# ap-pam-VX.net
KiCad netlist of a schematic drawn in Altium Designer
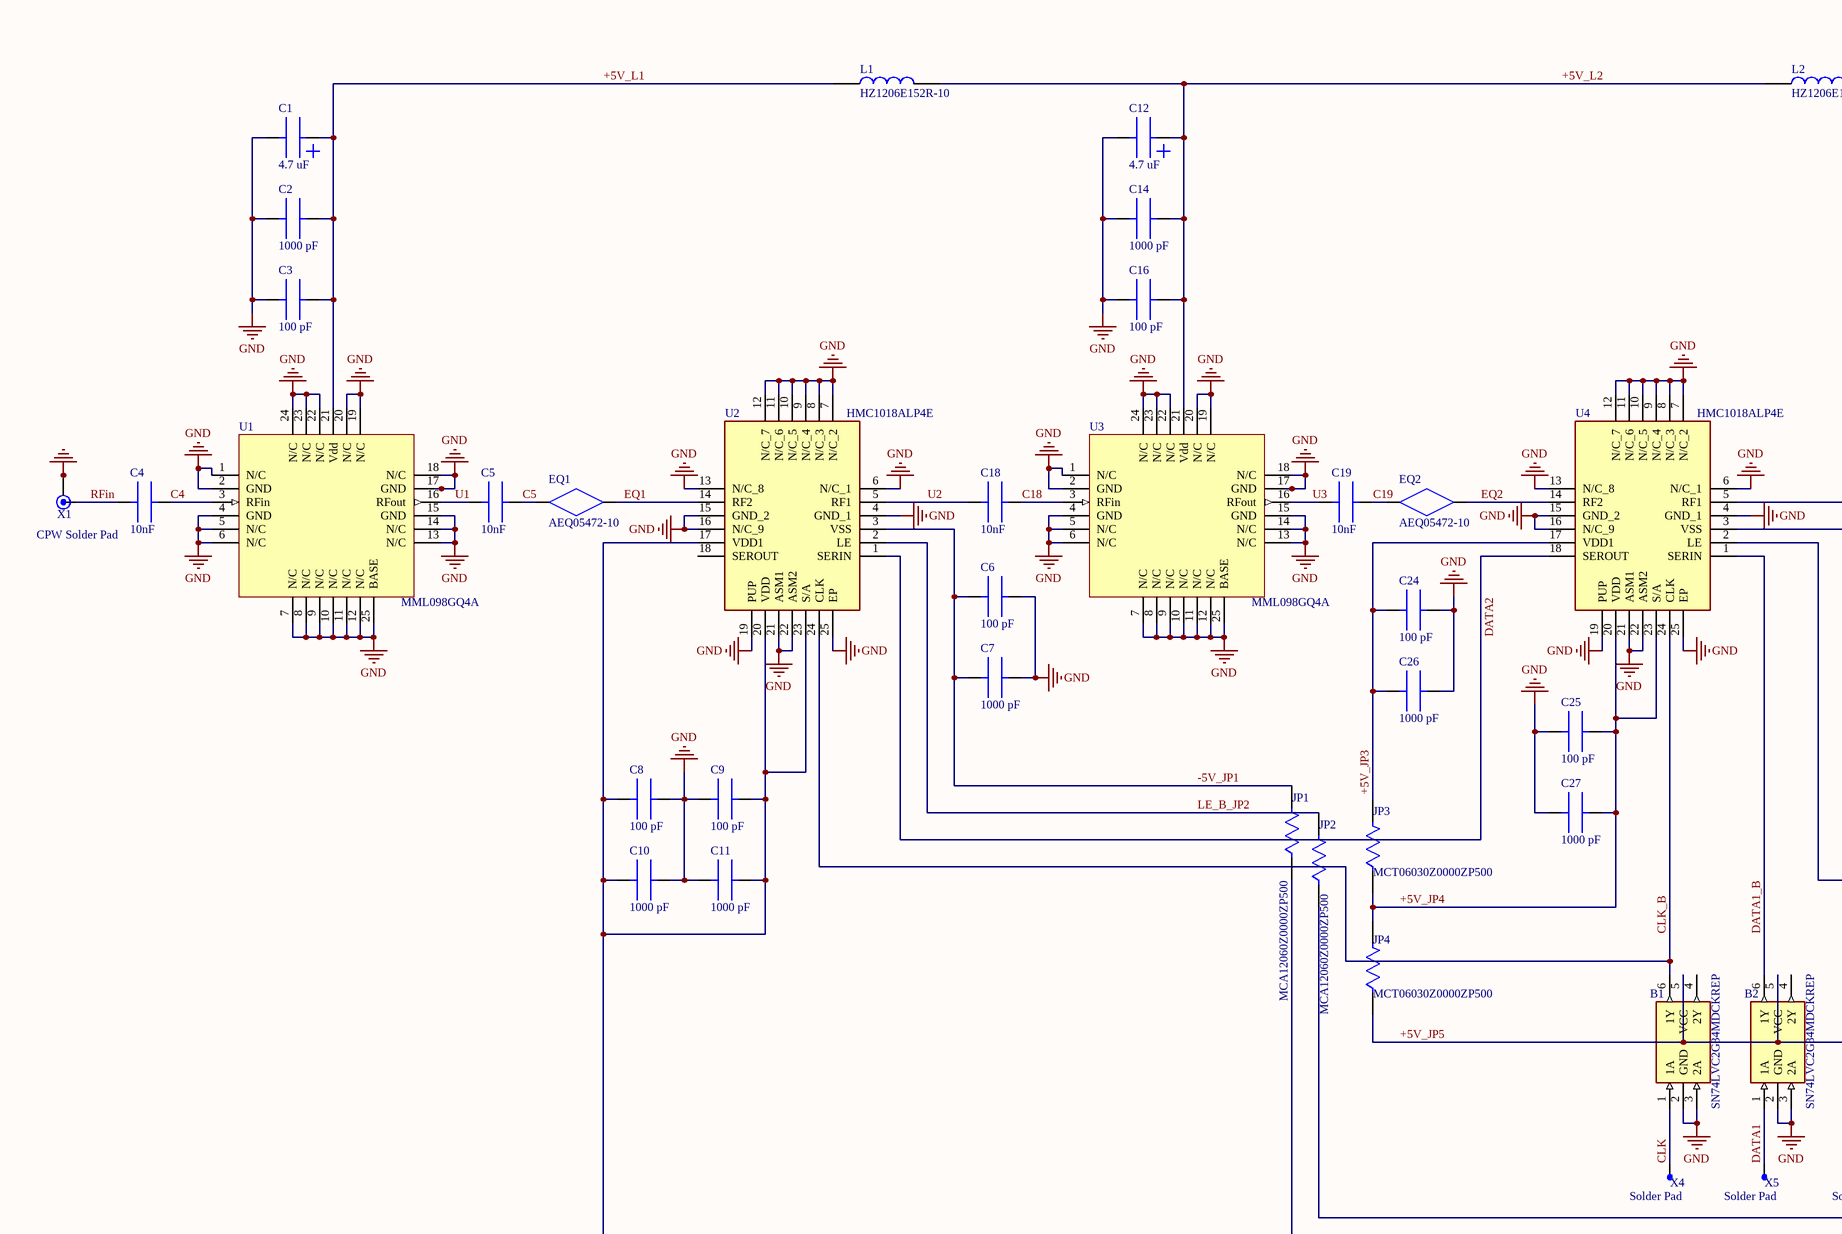
[diagram p0: ap-pam-VX.SchDoc, top left]
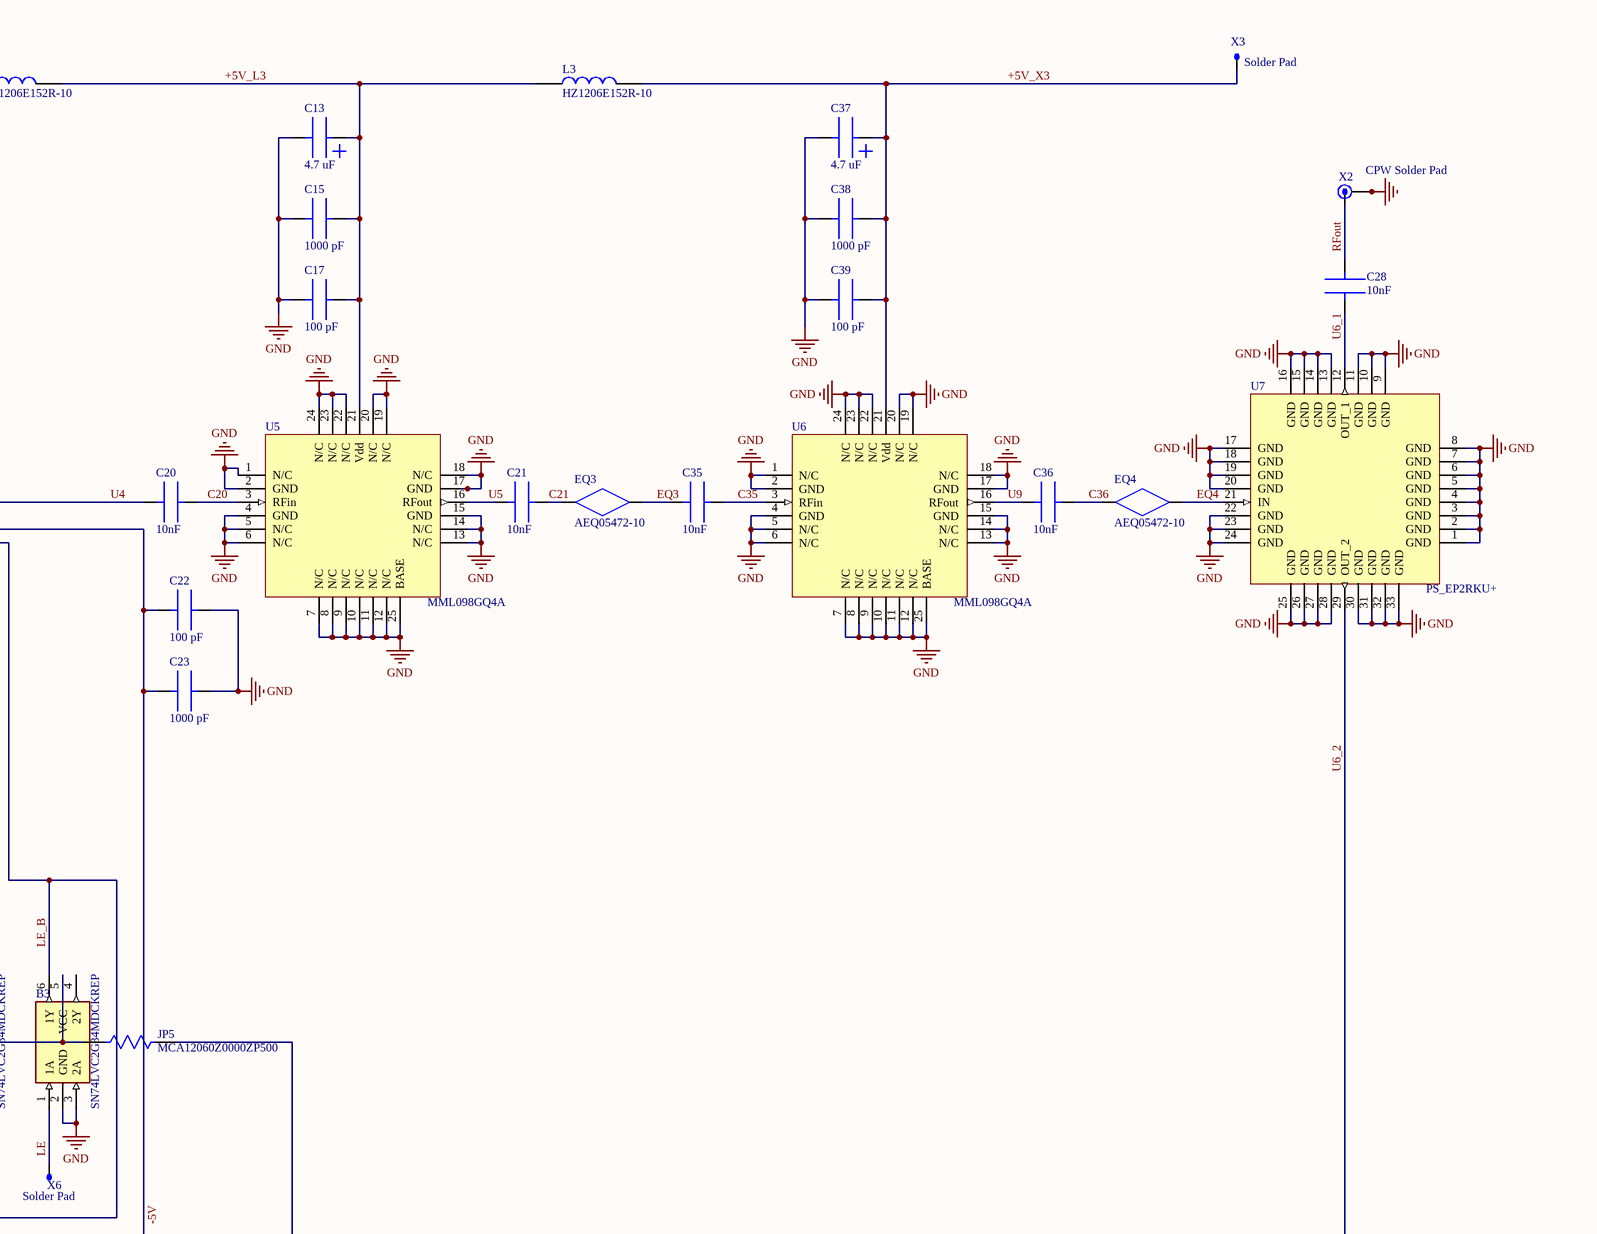
[diagram p1: ap-pam-VX.SchDoc, top right]
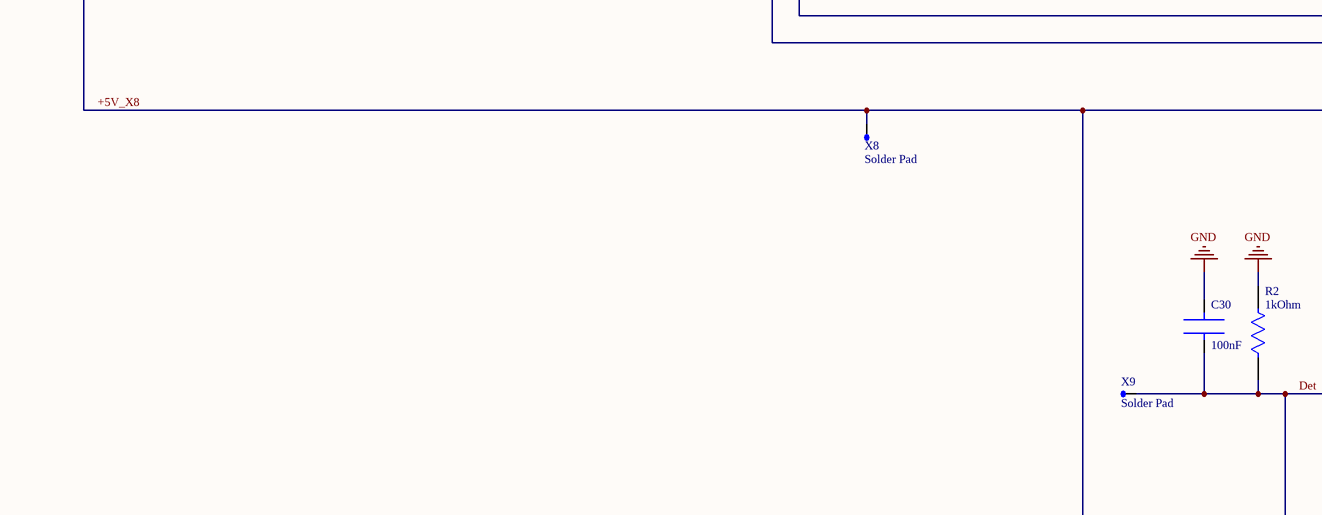
[diagram p2: ap-pam-VX.SchDoc, bottom left]
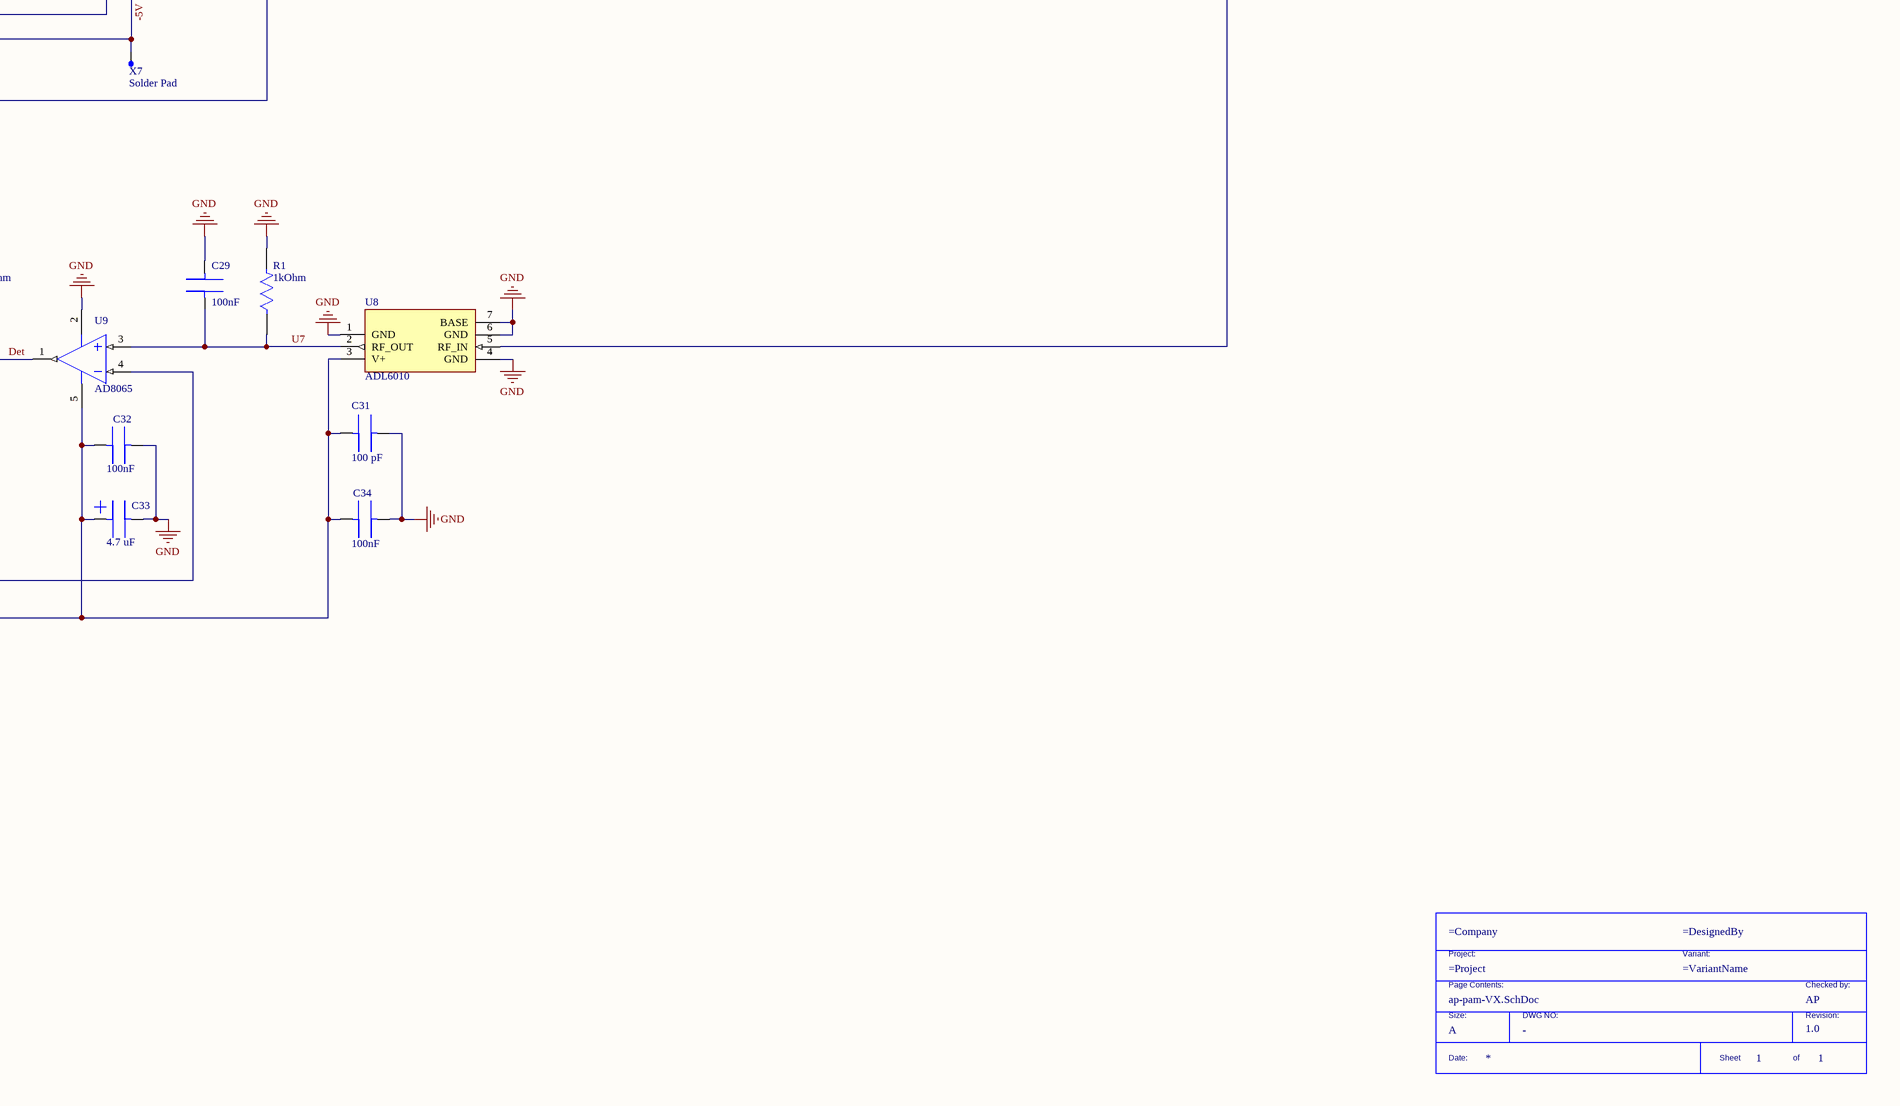
[diagram p3: ap-pam-VX.SchDoc, bottom right]

(export (version "E")
  (design (tool "Eeschema 10.0.6"))
  (components
    (comp (ref "*")
      (value "~")
      (description "Standard Title Block")
      (fields (field (name "DWG NO") "-") (field (name "SIZE") "A") (field (name "CHECKED BY") "AP"))
      (libsource (lib "ap-pam") (part "TitleBlock"))
    )
    (comp (ref "B1")
      (value "SN74LVC2G34MDCKREP")
      (footprint "buf_SN74LVC2G34MDCKREP")
      (description "Enhanced Product Dual Buffer Gate")
      (fields (field (name "MOUSER PART NUMBER") "595-SN74L2G34MDCKREP"))
      (libsource (lib "ap-pam") (part "Buf_SN74LVC2G34MDCKREP"))
    )
    (comp (ref "B2")
      (value "SN74LVC2G34MDCKREP")
      (footprint "buf_SN74LVC2G34MDCKREP")
      (description "Enhanced Product Dual Buffer Gate")
      (fields (field (name "MOUSER PART NUMBER") "595-SN74L2G34MDCKREP"))
      (libsource (lib "ap-pam") (part "Buf_SN74LVC2G34MDCKREP"))
    )
    (comp (ref "B3")
      (value "SN74LVC2G34MDCKREP")
      (footprint "buf_SN74LVC2G34MDCKREP")
      (description "Enhanced Product Dual Buffer Gate")
      (fields (field (name "MOUSER PART NUMBER") "595-SN74L2G34MDCKREP"))
      (libsource (lib "ap-pam") (part "Buf_SN74LVC2G34MDCKREP"))
    )
    (comp (ref "C1")
      (value "4.7 uF")
      (footprint "C4_7uF")
      (fields
        (field (name "MANUFACTURER") "Vishay Sprague")
        (field (name "MANUFACTURER PART NUMBER") "TH3A475K010C2900")
      )
      (libsource (lib "ap-pam") (part "C7_4uF_TH3A475K010C2900"))
    )
    (comp (ref "C2")
      (value "1000 pF")
      (footprint "C1000pF")
      (fields
        (field (name "MANUFACTURER") "Murata")
        (field (name "MANUFACTURER PART NUMBER") "GCM1885C1H102FA16D")
      )
      (libsource (lib "ap-pam") (part "GCM1885C1H102FA16D"))
    )
    (comp (ref "C3")
      (value "100 pF")
      (footprint "C100pF")
      (description "Multilayer Ceramic Capacitors MLCC - SMD/SMT 100 pF 100 VDC 1% 0402 C0G (NP0)")
      (fields
        (field (name "MANUFACTURER") "Murata")
        (field (name "MANUFACTURER PART NUMBER") "GRM1555C2A101FA01D")
      )
      (libsource (lib "ap-pam") (part "GRM1555C2A101FA01D"))
    )
    (comp (ref "C4")
      (value "10nF")
      (footprint "C10nF")
      (fields (field (name "MANUFACTURER") "Murata") (field (name "MANUFACTURER PART NUMBER") "939113733510"))
      (libsource (lib "ap-pam") (part "C10nF_939113733510"))
    )
    (comp (ref "C5")
      (value "10nF")
      (footprint "C10nF")
      (fields (field (name "MANUFACTURER") "Murata") (field (name "MANUFACTURER PART NUMBER") "939113733510"))
      (libsource (lib "ap-pam") (part "C10nF_939113733510"))
    )
    (comp (ref "C6")
      (value "100 pF")
      (footprint "C100pF")
      (description "Multilayer Ceramic Capacitors MLCC - SMD/SMT 100 pF 100 VDC 1% 0402 C0G (NP0)")
      (fields
        (field (name "MANUFACTURER") "Murata")
        (field (name "MANUFACTURER PART NUMBER") "GRM1555C2A101FA01D")
      )
      (libsource (lib "ap-pam") (part "GRM1555C2A101FA01D"))
    )
    (comp (ref "C7")
      (value "1000 pF")
      (footprint "C1000pF")
      (fields
        (field (name "MANUFACTURER") "Murata")
        (field (name "MANUFACTURER PART NUMBER") "GCM1885C1H102FA16D")
      )
      (libsource (lib "ap-pam") (part "GCM1885C1H102FA16D"))
    )
    (comp (ref "C8")
      (value "100 pF")
      (footprint "C100pF")
      (description "Multilayer Ceramic Capacitors MLCC - SMD/SMT 100 pF 100 VDC 1% 0402 C0G (NP0)")
      (fields
        (field (name "MANUFACTURER") "Murata")
        (field (name "MANUFACTURER PART NUMBER") "GRM1555C2A101FA01D")
      )
      (libsource (lib "ap-pam") (part "GRM1555C2A101FA01D"))
    )
    (comp (ref "C9")
      (value "100 pF")
      (footprint "C100pF")
      (description "Multilayer Ceramic Capacitors MLCC - SMD/SMT 100 pF 100 VDC 1% 0402 C0G (NP0)")
      (fields
        (field (name "MANUFACTURER") "Murata")
        (field (name "MANUFACTURER PART NUMBER") "GRM1555C2A101FA01D")
      )
      (libsource (lib "ap-pam") (part "GRM1555C2A101FA01D"))
    )
    (comp (ref "C10")
      (value "1000 pF")
      (footprint "C1000pF")
      (fields
        (field (name "MANUFACTURER") "Murata")
        (field (name "MANUFACTURER PART NUMBER") "GCM1885C1H102FA16D")
      )
      (libsource (lib "ap-pam") (part "GCM1885C1H102FA16D"))
    )
    (comp (ref "C11")
      (value "1000 pF")
      (footprint "C1000pF")
      (fields
        (field (name "MANUFACTURER") "Murata")
        (field (name "MANUFACTURER PART NUMBER") "GCM1885C1H102FA16D")
      )
      (libsource (lib "ap-pam") (part "GCM1885C1H102FA16D"))
    )
    (comp (ref "C12")
      (value "4.7 uF")
      (footprint "C4_7uF")
      (fields
        (field (name "MANUFACTURER") "Vishay Sprague")
        (field (name "MANUFACTURER PART NUMBER") "TH3A475K010C2900")
      )
      (libsource (lib "ap-pam") (part "C7_4uF_TH3A475K010C2900"))
    )
    (comp (ref "C13")
      (value "4.7 uF")
      (footprint "C4_7uF")
      (fields
        (field (name "MANUFACTURER") "Vishay Sprague")
        (field (name "MANUFACTURER PART NUMBER") "TH3A475K010C2900")
      )
      (libsource (lib "ap-pam") (part "C7_4uF_TH3A475K010C2900"))
    )
    (comp (ref "C14")
      (value "1000 pF")
      (footprint "C1000pF")
      (fields
        (field (name "MANUFACTURER") "Murata")
        (field (name "MANUFACTURER PART NUMBER") "GCM1885C1H102FA16D")
      )
      (libsource (lib "ap-pam") (part "GCM1885C1H102FA16D"))
    )
    (comp (ref "C15")
      (value "1000 pF")
      (footprint "C1000pF")
      (fields
        (field (name "MANUFACTURER") "Murata")
        (field (name "MANUFACTURER PART NUMBER") "GCM1885C1H102FA16D")
      )
      (libsource (lib "ap-pam") (part "GCM1885C1H102FA16D"))
    )
    (comp (ref "C16")
      (value "100 pF")
      (footprint "C100pF")
      (description "Multilayer Ceramic Capacitors MLCC - SMD/SMT 100 pF 100 VDC 1% 0402 C0G (NP0)")
      (fields
        (field (name "MANUFACTURER") "Murata")
        (field (name "MANUFACTURER PART NUMBER") "GRM1555C2A101FA01D")
      )
      (libsource (lib "ap-pam") (part "GRM1555C2A101FA01D"))
    )
    (comp (ref "C17")
      (value "100 pF")
      (footprint "C100pF")
      (description "Multilayer Ceramic Capacitors MLCC - SMD/SMT 100 pF 100 VDC 1% 0402 C0G (NP0)")
      (fields
        (field (name "MANUFACTURER") "Murata")
        (field (name "MANUFACTURER PART NUMBER") "GRM1555C2A101FA01D")
      )
      (libsource (lib "ap-pam") (part "GRM1555C2A101FA01D"))
    )
    (comp (ref "C18")
      (value "10nF")
      (footprint "C10nF")
      (fields (field (name "MANUFACTURER") "Murata") (field (name "MANUFACTURER PART NUMBER") "939113733510"))
      (libsource (lib "ap-pam") (part "C10nF_939113733510"))
    )
    (comp (ref "C19")
      (value "10nF")
      (footprint "C10nF")
      (fields (field (name "MANUFACTURER") "Murata") (field (name "MANUFACTURER PART NUMBER") "939113733510"))
      (libsource (lib "ap-pam") (part "C10nF_939113733510"))
    )
    (comp (ref "C20")
      (value "10nF")
      (footprint "C10nF")
      (fields (field (name "MANUFACTURER") "Murata") (field (name "MANUFACTURER PART NUMBER") "939113733510"))
      (libsource (lib "ap-pam") (part "C10nF_939113733510"))
    )
    (comp (ref "C21")
      (value "10nF")
      (footprint "C10nF")
      (fields (field (name "MANUFACTURER") "Murata") (field (name "MANUFACTURER PART NUMBER") "939113733510"))
      (libsource (lib "ap-pam") (part "C10nF_939113733510"))
    )
    (comp (ref "C22")
      (value "100 pF")
      (footprint "C100pF")
      (description "Multilayer Ceramic Capacitors MLCC - SMD/SMT 100 pF 100 VDC 1% 0402 C0G (NP0)")
      (fields
        (field (name "MANUFACTURER") "Murata")
        (field (name "MANUFACTURER PART NUMBER") "GRM1555C2A101FA01D")
      )
      (libsource (lib "ap-pam") (part "GRM1555C2A101FA01D"))
    )
    (comp (ref "C23")
      (value "1000 pF")
      (footprint "C1000pF")
      (fields
        (field (name "MANUFACTURER") "Murata")
        (field (name "MANUFACTURER PART NUMBER") "GCM1885C1H102FA16D")
      )
      (libsource (lib "ap-pam") (part "GCM1885C1H102FA16D"))
    )
    (comp (ref "C24")
      (value "100 pF")
      (footprint "C100pF")
      (description "Multilayer Ceramic Capacitors MLCC - SMD/SMT 100 pF 100 VDC 1% 0402 C0G (NP0)")
      (fields
        (field (name "MANUFACTURER") "Murata")
        (field (name "MANUFACTURER PART NUMBER") "GRM1555C2A101FA01D")
      )
      (libsource (lib "ap-pam") (part "GRM1555C2A101FA01D"))
    )
    (comp (ref "C25")
      (value "100 pF")
      (footprint "C100pF")
      (description "Multilayer Ceramic Capacitors MLCC - SMD/SMT 100 pF 100 VDC 1% 0402 C0G (NP0)")
      (fields
        (field (name "MANUFACTURER") "Murata")
        (field (name "MANUFACTURER PART NUMBER") "GRM1555C2A101FA01D")
      )
      (libsource (lib "ap-pam") (part "GRM1555C2A101FA01D"))
    )
    (comp (ref "C26")
      (value "1000 pF")
      (footprint "C1000pF")
      (fields
        (field (name "MANUFACTURER") "Murata")
        (field (name "MANUFACTURER PART NUMBER") "GCM1885C1H102FA16D")
      )
      (libsource (lib "ap-pam") (part "GCM1885C1H102FA16D"))
    )
    (comp (ref "C27")
      (value "1000 pF")
      (footprint "C1000pF")
      (fields
        (field (name "MANUFACTURER") "Murata")
        (field (name "MANUFACTURER PART NUMBER") "GCM1885C1H102FA16D")
      )
      (libsource (lib "ap-pam") (part "GCM1885C1H102FA16D"))
    )
    (comp (ref "C28")
      (value "10nF")
      (footprint "C10nF")
      (fields (field (name "MANUFACTURER") "Murata") (field (name "MANUFACTURER PART NUMBER") "939113733510"))
      (libsource (lib "ap-pam") (part "C10nF_939113733510"))
    )
    (comp (ref "C29")
      (value "100nF")
      (footprint "C1000pF__C100nF")
      (fields
        (field (name "MANUFACTURER") "Murata")
        (field (name "MANUFACTURER PART NUMBER") "GCM188R71C104KA37J")
      )
      (libsource (lib "ap-pam") (part "C100nF_GCM188R71C104KA37J"))
    )
    (comp (ref "C30")
      (value "100nF")
      (footprint "C1000pF__C100nF")
      (fields
        (field (name "MANUFACTURER") "Murata")
        (field (name "MANUFACTURER PART NUMBER") "GCM188R71C104KA37J")
      )
      (libsource (lib "ap-pam") (part "C100nF_GCM188R71C104KA37J"))
    )
    (comp (ref "C31")
      (value "100 pF")
      (footprint "C100pF")
      (description "Multilayer Ceramic Capacitors MLCC - SMD/SMT 100 pF 100 VDC 1% 0402 C0G (NP0)")
      (fields
        (field (name "MANUFACTURER") "Murata")
        (field (name "MANUFACTURER PART NUMBER") "GRM1555C2A101FA01D")
      )
      (libsource (lib "ap-pam") (part "C100pF_GRM1555C2A101FA01D"))
    )
    (comp (ref "C32")
      (value "100nF")
      (footprint "C1000pF__C100nF")
      (fields
        (field (name "MANUFACTURER") "Murata")
        (field (name "MANUFACTURER PART NUMBER") "GCM188R71C104KA37J")
      )
      (libsource (lib "ap-pam") (part "C100nF_GCM188R71C104KA37J"))
    )
    (comp (ref "C33")
      (value "4.7 uF")
      (footprint "C4_7uF")
      (fields
        (field (name "MANUFACTURER") "Vishay Sprague")
        (field (name "MANUFACTURER PART NUMBER") "TH3A475K010C2900")
      )
      (libsource (lib "ap-pam") (part "C7_4uF_TH3A475K010C2900"))
    )
    (comp (ref "C34")
      (value "100nF")
      (footprint "C1000pF__C100nF")
      (fields
        (field (name "MANUFACTURER") "Murata")
        (field (name "MANUFACTURER PART NUMBER") "GCM188R71C104KA37J")
      )
      (libsource (lib "ap-pam") (part "C100nF_GCM188R71C104KA37J"))
    )
    (comp (ref "C35")
      (value "10nF")
      (footprint "C10nF")
      (fields (field (name "MANUFACTURER") "Murata") (field (name "MANUFACTURER PART NUMBER") "939113733510"))
      (libsource (lib "ap-pam") (part "C10nF_939113733510"))
    )
    (comp (ref "C36")
      (value "10nF")
      (footprint "C10nF")
      (fields (field (name "MANUFACTURER") "Murata") (field (name "MANUFACTURER PART NUMBER") "939113733510"))
      (libsource (lib "ap-pam") (part "C10nF_939113733510"))
    )
    (comp (ref "C37")
      (value "4.7 uF")
      (footprint "C4_7uF")
      (fields
        (field (name "MANUFACTURER") "Vishay Sprague")
        (field (name "MANUFACTURER PART NUMBER") "TH3A475K010C2900")
      )
      (libsource (lib "ap-pam") (part "C7_4uF_TH3A475K010C2900"))
    )
    (comp (ref "C38")
      (value "1000 pF")
      (footprint "C1000pF__C100nF")
      (fields
        (field (name "MANUFACTURER") "Murata")
        (field (name "MANUFACTURER PART NUMBER") "GCM1885C1H102FA16D")
      )
      (libsource (lib "ap-pam") (part "C1000pF_GCM1885C1H102FA16D"))
    )
    (comp (ref "C39")
      (value "100 pF")
      (footprint "C100pF")
      (description "Multilayer Ceramic Capacitors MLCC - SMD/SMT 100 pF 100 VDC 1% 0402 C0G (NP0)")
      (fields
        (field (name "MANUFACTURER") "Murata")
        (field (name "MANUFACTURER PART NUMBER") "GRM1555C2A101FA01D")
      )
      (libsource (lib "ap-pam") (part "C100pF_GRM1555C2A101FA01D"))
    )
    (comp (ref "EQ1")
      (value "AEQ05472-10")
      (footprint "EQ_AEQ05472")
      (description "Rf Filter Gain Equalizer 2SMD")
      (fields (field (name "MANUFACTURER") "Knowles Dielectric Labs"))
      (libsource (lib "ap-pam") (part "EQ_AEQ05472-10"))
    )
    (comp (ref "EQ2")
      (value "AEQ05472-10")
      (footprint "EQ_AEQ05472")
      (description "Rf Filter Gain Equalizer 2SMD")
      (fields (field (name "MANUFACTURER") "Knowles Dielectric Labs"))
      (libsource (lib "ap-pam") (part "EQ_AEQ05472-10"))
    )
    (comp (ref "EQ3")
      (value "AEQ05472-10")
      (footprint "EQ_AEQ05472")
      (description "Rf Filter Gain Equalizer 2SMD")
      (fields (field (name "MANUFACTURER") "Knowles Dielectric Labs"))
      (libsource (lib "ap-pam") (part "EQ_AEQ05472-10"))
    )
    (comp (ref "EQ4")
      (value "AEQ05472-10")
      (footprint "EQ_AEQ05472")
      (description "Rf Filter Gain Equalizer 2SMD")
      (fields (field (name "MANUFACTURER") "Knowles Dielectric Labs"))
      (libsource (lib "ap-pam") (part "EQ_AEQ05472-10"))
    )
    (comp (ref "JP1")
      (value "MCA12060Z0000ZP500")
      (footprint "JP_MCA12060Z0000ZP500")
      (description "Fixed Resistor, Thin Film, 0.25W, 0ohm, Surface Mount, 1206")
      (fields (field (name "MANUFACTURER") "Vishay") (field (name "POWER") "250mW"))
      (libsource (lib "ap-pam") (part "JP_MCA12060Z0000ZP500"))
    )
    (comp (ref "JP2")
      (value "MCA12060Z0000ZP500")
      (footprint "JP_MCA12060Z0000ZP500")
      (description "Fixed Resistor, Thin Film, 0.25W, 0ohm, Surface Mount, 1206")
      (fields (field (name "MANUFACTURER") "Vishay") (field (name "POWER") "250mW"))
      (libsource (lib "ap-pam") (part "JP_MCA12060Z0000ZP500"))
    )
    (comp (ref "JP3")
      (value "MCT06030Z0000ZP500")
      (footprint "JP_small_MCT06030Z0000ZP500")
      (description "Fixed Resistor, Thin Film, 0.1W, 0ohm, Surface Mount, 0603")
      (fields (field (name "MANUFACTURER") "Vishay Beyschlag") (field (name "POWER") "100mW"))
      (libsource (lib "ap-pam") (part "JP_small_MCT06030Z0000ZP500"))
    )
    (comp (ref "JP4")
      (value "MCT06030Z0000ZP500")
      (footprint "JP_small_MCT06030Z0000ZP500")
      (description "Fixed Resistor, Thin Film, 0.1W, 0ohm, Surface Mount, 0603")
      (fields (field (name "MANUFACTURER") "Vishay Beyschlag") (field (name "POWER") "100mW"))
      (libsource (lib "ap-pam") (part "JP_small_MCT06030Z0000ZP500"))
    )
    (comp (ref "JP5")
      (value "MCA12060Z0000ZP500")
      (footprint "JP_MCA12060Z0000ZP500")
      (description "Fixed Resistor, Thin Film, 0.25W, 0ohm, Surface Mount, 1206")
      (fields (field (name "MANUFACTURER") "Vishay") (field (name "POWER") "250mW"))
      (libsource (lib "ap-pam") (part "JP_MCA12060Z0000ZP500"))
    )
    (comp (ref "L1")
      (value "HZ1206E152R-10")
      (footprint "FB_HZ1206E152R-10")
      (description "Ferrite Chip, 1 Function(s), 0.5A, 2 Pin(s)")
      (fields (field (name "MANUFACTURER") "Laird"))
      (libsource (lib "ap-pam") (part "FB_HZ1206E152R-10"))
    )
    (comp (ref "L2")
      (value "HZ1206E152R-10")
      (footprint "FB_HZ1206E152R-10")
      (description "Ferrite Chip, 1 Function(s), 0.5A, 2 Pin(s)")
      (fields (field (name "MANUFACTURER") "Laird"))
      (libsource (lib "ap-pam") (part "FB_HZ1206E152R-10"))
    )
    (comp (ref "L3")
      (value "HZ1206E152R-10")
      (footprint "FB_HZ1206E152R-10")
      (description "Ferrite Chip, 1 Function(s), 0.5A, 2 Pin(s)")
      (fields (field (name "MANUFACTURER") "Laird"))
      (libsource (lib "ap-pam") (part "FB_HZ1206E152R-10"))
    )
    (comp (ref "R1")
      (value "1kOhm")
      (footprint "JP_R_MCT06030Z0000ZP500")
      (description "Fixed Resistor, Thin Film, 0.1W, 1000ohm, 75V, 1% +/-Tol, 50ppm/Cel, Surface Mount, 0603")
      (fields
        (field (name "MANUFACTURER") "Vishay BCcomponents")
        (field (name "MANUFACTURER PART NUMBER") "MCT06030C1001FPW00")
      )
      (libsource (lib "ap-pam") (part "R_1kOhm_MCT06030C1001FPW00"))
    )
    (comp (ref "R2")
      (value "1kOhm")
      (footprint "JP_R_MCT06030Z0000ZP500")
      (description "Fixed Resistor, Thin Film, 0.1W, 1000ohm, 75V, 1% +/-Tol, 50ppm/Cel, Surface Mount, 0603")
      (fields
        (field (name "MANUFACTURER") "Vishay BCcomponents")
        (field (name "MANUFACTURER PART NUMBER") "MCT06030C1001FPW00")
      )
      (libsource (lib "ap-pam") (part "R_1kOhm_MCT06030C1001FPW00"))
    )
    (comp (ref "U1")
      (value "MML098GQ4A")
      (footprint "amp_MML098GQ4A")
      (libsource (lib "ap-pam") (part "amp_MML098GQ4A"))
    )
    (comp (ref "U2")
      (value "HMC1018ALP4E")
      (footprint "Att_HMC101018ALPE")
      (description "Attenuators Attenuators")
      (fields (field (name "MOUSER PART NUMBER") "584-HMC1018ALP4E"))
      (libsource (lib "ap-pam") (part "Att_HMC1018ALP4E"))
    )
    (comp (ref "U3")
      (value "MML098GQ4A")
      (footprint "amp_MML098GQ4A")
      (libsource (lib "ap-pam") (part "amp_MML098GQ4A"))
    )
    (comp (ref "U4")
      (value "HMC1018ALP4E")
      (footprint "Att_HMC101018ALPE")
      (description "Attenuators Attenuators")
      (fields (field (name "MOUSER PART NUMBER") "584-HMC1018ALP4E"))
      (libsource (lib "ap-pam") (part "Att_HMC1018ALP4E"))
    )
    (comp (ref "U5")
      (value "MML098GQ4A")
      (footprint "amp_MML098GQ4A")
      (libsource (lib "ap-pam") (part "amp_MML098GQ4A"))
    )
    (comp (ref "U6")
      (value "MML098GQ4A")
      (footprint "amp_MML098GQ4A")
      (libsource (lib "") (part "amp_MML098GQ4A_1"))
    )
    (comp (ref "U7")
      (value "PS_EP2RKU+")
      (footprint "PS_EP2RKU+")
      (description "Splitter And Combiner")
      (fields
        (field (name "MANUFACTURER") "Mini-Circuits")
        (field (name "MANUFACTURER PART NUMBER") "EP2RKU+")
      )
      (libsource (lib "ap-pam") (part "PS_EP2RKU+"))
    )
    (comp (ref "U8")
      (value "ADL6010")
      (footprint "Det_ADL6010ACPZN-R2")
      (description "Linear Detector, 500MHz Min, 43500MHz Max, 20dBm Input Power-Max")
      (fields
        (field (name "MANUFACTURER") "Analog Devices")
        (field (name "MANUFACTURER PART NUMBER") "ADL6010ACPZN-R2")
      )
      (libsource (lib "ap-pam") (part "det_ADL6010ACPZN-R2"))
    )
    (comp (ref "U9")
      (value "AD8065")
      (footprint "opAmp_AD8065ARTZ-REEL7")
      (description "Operational Amplifier, 1 Func, BIPolar, PDSO5")
      (fields
        (field (name "MANUFACTURER") "Analog Devices")
        (field (name "MANUFACTURER PART NUMBER") "AD8065ARTZ-REEL7")
      )
      (libsource (lib "ap-pam") (part "opAmp_AD8065ARTZ-REEL7"))
    )
    (comp (ref "X1")
      (value "CPW Solder Pad")
      (footprint "CPW Edge Connector")
      (description "Solder pad for RF Coplanar Waveguide Rogers 4350B Thickness 0.020\" Copper 1oz")
      (libsource (lib "ap-pam") (part "RF  CPW Solder Pad"))
    )
    (comp (ref "X2")
      (value "CPW Solder Pad")
      (footprint "CPW Edge Connector")
      (description "Solder pad for RF Coplanar Waveguide Rogers 4350B Thickness 0.020\" Copper 1oz")
      (libsource (lib "ap-pam") (part "RF  CPW Solder Pad"))
    )
    (comp (ref "X3")
      (value "Solder Pad")
      (footprint "Solder Pad")
      (description "Pad to solder wires to")
      (libsource (lib "ap-pam") (part "Solder Pad"))
    )
    (comp (ref "X4")
      (value "Solder Pad")
      (footprint "Solder Pad")
      (description "Pad to solder wires to")
      (libsource (lib "ap-pam") (part "Solder Pad"))
    )
    (comp (ref "X5")
      (value "Solder Pad")
      (footprint "Solder Pad")
      (description "Pad to solder wires to")
      (libsource (lib "ap-pam") (part "Solder Pad"))
    )
    (comp (ref "X6")
      (value "Solder Pad")
      (footprint "Solder Pad")
      (description "Pad to solder wires to")
      (libsource (lib "ap-pam") (part "Solder Pad"))
    )
    (comp (ref "X7")
      (value "Solder Pad")
      (footprint "Solder Pad")
      (description "Pad to solder wires to")
      (libsource (lib "ap-pam") (part "Solder Pad"))
    )
    (comp (ref "X8")
      (value "Solder Pad")
      (footprint "Solder Pad")
      (description "Pad to solder wires to")
      (libsource (lib "ap-pam") (part "Solder Pad"))
    )
    (comp (ref "X9")
      (value "Solder Pad")
      (footprint "Solder Pad")
      (description "Pad to solder wires to")
      (libsource (lib "ap-pam") (part "Solder Pad"))
    )
  )
  (nets
    (net (code "1") (name "/+5V_JP3") (class "Default")
      (node (ref "C24") (pin "1") (pinfunction "1_1") (pintype "passive"))
      (node (ref "C26") (pin "1") (pinfunction "1_1") (pintype "passive"))
      (node (ref "JP3") (pin "2") (pinfunction "2_2") (pintype "passive"))
      (node (ref "U4") (pin "17") (pinfunction "VDD1_17") (pintype "passive"))
    )
    (net (code "2") (name "/+5V_JP4") (class "Default")
      (node (ref "C25") (pin "1") (pinfunction "1_1") (pintype "passive"))
      (node (ref "C27") (pin "1") (pinfunction "1_1") (pintype "passive"))
      (node (ref "JP3") (pin "1") (pinfunction "1_1") (pintype "passive"))
      (node (ref "JP4") (pin "2") (pinfunction "2_2") (pintype "passive"))
      (node (ref "U4") (pin "20") (pinfunction "VDD_20") (pintype "passive"))
      (node (ref "U4") (pin "23") (pinfunction "S/A_23") (pintype "passive"))
    )
    (net (code "3") (name "/+5V_JP5") (class "Default")
      (node (ref "B1") (pin "5") (pinfunction "VCC_5") (pintype "passive"))
      (node (ref "B2") (pin "5") (pinfunction "VCC_5") (pintype "passive"))
      (node (ref "B3") (pin "5") (pinfunction "VCC_5") (pintype "passive"))
      (node (ref "JP4") (pin "1") (pinfunction "1_1") (pintype "passive"))
      (node (ref "JP5") (pin "1") (pinfunction "1_1") (pintype "passive"))
    )
    (net (code "4") (name "/+5V_L1") (class "Default")
      (node (ref "C1") (pin "1") (pinfunction "+_1") (pintype "passive"))
      (node (ref "C2") (pin "1") (pinfunction "1_1") (pintype "passive"))
      (node (ref "C3") (pin "1") (pinfunction "1_1") (pintype "passive"))
      (node (ref "L1") (pin "1") (pinfunction "1_1") (pintype "passive"))
      (node (ref "U1") (pin "21") (pinfunction "Vdd_21") (pintype "power_in"))
    )
    (net (code "5") (name "/+5V_L2") (class "Default")
      (node (ref "C12") (pin "1") (pinfunction "+_1") (pintype "passive"))
      (node (ref "C14") (pin "1") (pinfunction "1_1") (pintype "passive"))
      (node (ref "C16") (pin "1") (pinfunction "1_1") (pintype "passive"))
      (node (ref "L1") (pin "2") (pinfunction "2_2") (pintype "passive"))
      (node (ref "L2") (pin "1") (pinfunction "1_1") (pintype "passive"))
      (node (ref "U3") (pin "21") (pinfunction "Vdd_21") (pintype "power_in"))
    )
    (net (code "6") (name "/+5V_L3") (class "Default")
      (node (ref "C13") (pin "1") (pinfunction "+_1") (pintype "passive"))
      (node (ref "C15") (pin "1") (pinfunction "1_1") (pintype "passive"))
      (node (ref "C17") (pin "1") (pinfunction "1_1") (pintype "passive"))
      (node (ref "L2") (pin "2") (pinfunction "2_2") (pintype "passive"))
      (node (ref "L3") (pin "1") (pinfunction "1_1") (pintype "passive"))
      (node (ref "U5") (pin "21") (pinfunction "Vdd_21") (pintype "power_in"))
    )
    (net (code "7") (name "/+5V_X3") (class "Default")
      (node (ref "C37") (pin "1") (pinfunction "+_1") (pintype "passive"))
      (node (ref "C38") (pin "1") (pinfunction "1_1") (pintype "passive"))
      (node (ref "C39") (pin "1") (pinfunction "1_1") (pintype "passive"))
      (node (ref "L3") (pin "2") (pinfunction "2_2") (pintype "passive"))
      (node (ref "U6") (pin "21") (pinfunction "Vdd_21") (pintype "power_in"))
      (node (ref "X3") (pin "1") (pinfunction "1_1") (pintype "passive"))
    )
    (net (code "8") (name "/+5V_X8") (class "Default")
      (node (ref "C10") (pin "1") (pinfunction "1_1") (pintype "passive"))
      (node (ref "C11") (pin "1") (pinfunction "1_1") (pintype "passive"))
      (node (ref "C31") (pin "2") (pinfunction "2_2") (pintype "passive"))
      (node (ref "C32") (pin "2") (pinfunction "2_2") (pintype "passive"))
      (node (ref "C33") (pin "1") (pinfunction "+_1") (pintype "passive"))
      (node (ref "C34") (pin "2") (pinfunction "2_2") (pintype "passive"))
      (node (ref "C8") (pin "1") (pinfunction "1_1") (pintype "passive"))
      (node (ref "C9") (pin "1") (pinfunction "1_1") (pintype "passive"))
      (node (ref "JP5") (pin "2") (pinfunction "2_2") (pintype "passive"))
      (node (ref "U2") (pin "17") (pinfunction "VDD1_17") (pintype "passive"))
      (node (ref "U2") (pin "20") (pinfunction "VDD_20") (pintype "passive"))
      (node (ref "U2") (pin "23") (pinfunction "S/A_23") (pintype "passive"))
      (node (ref "U8") (pin "3") (pinfunction "V+_3") (pintype "passive"))
      (node (ref "U9") (pin "5") (pinfunction "+VS_5") (pintype "power_in"))
      (node (ref "X8") (pin "1") (pinfunction "1_1") (pintype "passive"))
    )
    (net (code "9") (name "/-5V") (class "Default")
      (node (ref "C22") (pin "1") (pinfunction "1_1") (pintype "passive"))
      (node (ref "C23") (pin "1") (pinfunction "1_1") (pintype "passive"))
      (node (ref "JP1") (pin "1") (pinfunction "1_1") (pintype "passive"))
      (node (ref "U4") (pin "3") (pinfunction "VSS_3") (pintype "passive"))
      (node (ref "X7") (pin "1") (pinfunction "1_1") (pintype "passive"))
    )
    (net (code "10") (name "/-5V_JP1") (class "Default")
      (node (ref "C6") (pin "1") (pinfunction "1_1") (pintype "passive"))
      (node (ref "C7") (pin "1") (pinfunction "1_1") (pintype "passive"))
      (node (ref "JP1") (pin "2") (pinfunction "2_2") (pintype "passive"))
      (node (ref "U2") (pin "3") (pinfunction "VSS_3") (pintype "passive"))
    )
    (net (code "11") (name "/C4") (class "Default")
      (node (ref "C4") (pin "2") (pinfunction "2_2") (pintype "passive"))
      (node (ref "U1") (pin "3") (pinfunction "RFin_3") (pintype "input"))
    )
    (net (code "12") (name "/C5") (class "Default")
      (node (ref "C5") (pin "2") (pinfunction "2_2") (pintype "passive"))
      (node (ref "EQ1") (pin "1") (pinfunction "1_1") (pintype "passive"))
    )
    (net (code "13") (name "/C18") (class "Default")
      (node (ref "C18") (pin "2") (pinfunction "2_2") (pintype "passive"))
      (node (ref "U3") (pin "3") (pinfunction "RFin_3") (pintype "input"))
    )
    (net (code "14") (name "/C19") (class "Default")
      (node (ref "C19") (pin "2") (pinfunction "2_2") (pintype "passive"))
      (node (ref "EQ2") (pin "1") (pinfunction "1_1") (pintype "passive"))
    )
    (net (code "15") (name "/C20") (class "Default")
      (node (ref "C20") (pin "2") (pinfunction "2_2") (pintype "passive"))
      (node (ref "U5") (pin "3") (pinfunction "RFin_3") (pintype "input"))
    )
    (net (code "16") (name "/C21") (class "Default")
      (node (ref "C21") (pin "2") (pinfunction "2_2") (pintype "passive"))
      (node (ref "EQ3") (pin "1") (pinfunction "1_1") (pintype "passive"))
    )
    (net (code "17") (name "/C35") (class "Default")
      (node (ref "C35") (pin "2") (pinfunction "2_2") (pintype "passive"))
      (node (ref "U6") (pin "3") (pinfunction "RFin_3") (pintype "input"))
    )
    (net (code "18") (name "/C36") (class "Default")
      (node (ref "C36") (pin "2") (pinfunction "2_2") (pintype "passive"))
      (node (ref "EQ4") (pin "1") (pinfunction "1_1") (pintype "passive"))
    )
    (net (code "19") (name "/CLK") (class "Default")
      (node (ref "B1") (pin "1") (pinfunction "1A_1") (pintype "input"))
      (node (ref "X4") (pin "1") (pinfunction "1_1") (pintype "passive"))
    )
    (net (code "20") (name "/CLK_B") (class "Default")
      (node (ref "B1") (pin "6") (pinfunction "1Y_6") (pintype "output"))
      (node (ref "U2") (pin "24") (pinfunction "CLK_24") (pintype "passive"))
      (node (ref "U4") (pin "24") (pinfunction "CLK_24") (pintype "passive"))
    )
    (net (code "21") (name "/DATA1") (class "Default")
      (node (ref "B2") (pin "1") (pinfunction "1A_1") (pintype "input"))
      (node (ref "X5") (pin "1") (pinfunction "1_1") (pintype "passive"))
    )
    (net (code "22") (name "/DATA1_B") (class "Default")
      (node (ref "B2") (pin "6") (pinfunction "1Y_6") (pintype "output"))
      (node (ref "U4") (pin "1") (pinfunction "SERIN_1") (pintype "passive"))
    )
    (net (code "23") (name "/DATA2") (class "Default")
      (node (ref "U2") (pin "1") (pinfunction "SERIN_1") (pintype "passive"))
      (node (ref "U4") (pin "18") (pinfunction "SEROUT_18") (pintype "passive"))
    )
    (net (code "24") (name "/Det") (class "Default")
      (node (ref "C30") (pin "1") (pinfunction "1_1") (pintype "passive"))
      (node (ref "R2") (pin "1") (pinfunction "1_1") (pintype "passive"))
      (node (ref "U9") (pin "1") (pinfunction "VOUT_1") (pintype "output"))
      (node (ref "U9") (pin "4") (pinfunction "-IN_4") (pintype "input"))
      (node (ref "X9") (pin "1") (pinfunction "1_1") (pintype "passive"))
    )
    (net (code "25") (name "/EQ1") (class "Default")
      (node (ref "EQ1") (pin "2") (pinfunction "2_2") (pintype "passive"))
      (node (ref "U2") (pin "14") (pinfunction "RF2_14") (pintype "passive"))
    )
    (net (code "26") (name "/EQ2") (class "Default")
      (node (ref "EQ2") (pin "2") (pinfunction "2_2") (pintype "passive"))
      (node (ref "U4") (pin "14") (pinfunction "RF2_14") (pintype "passive"))
    )
    (net (code "27") (name "/EQ3") (class "Default")
      (node (ref "C35") (pin "1") (pinfunction "1_1") (pintype "passive"))
      (node (ref "EQ3") (pin "2") (pinfunction "2_2") (pintype "passive"))
    )
    (net (code "28") (name "/EQ4") (class "Default")
      (node (ref "EQ4") (pin "2") (pinfunction "2_2") (pintype "passive"))
      (node (ref "U7") (pin "21") (pinfunction "IN_21") (pintype "input"))
    )
    (net (code "29") (name "/LE") (class "Default")
      (node (ref "B3") (pin "1") (pinfunction "1A_1") (pintype "input"))
      (node (ref "X6") (pin "1") (pinfunction "1_1") (pintype "passive"))
    )
    (net (code "30") (name "/LE_B") (class "Default")
      (node (ref "B3") (pin "6") (pinfunction "1Y_6") (pintype "output"))
      (node (ref "JP2") (pin "1") (pinfunction "1_1") (pintype "passive"))
      (node (ref "U4") (pin "2") (pinfunction "LE_2") (pintype "passive"))
    )
    (net (code "31") (name "/LE_B_JP2") (class "Default")
      (node (ref "JP2") (pin "2") (pinfunction "2_2") (pintype "passive"))
      (node (ref "U2") (pin "2") (pinfunction "LE_2") (pintype "passive"))
    )
    (net (code "32") (name "/RFin") (class "Default")
      (node (ref "C4") (pin "1") (pinfunction "1_1") (pintype "passive"))
      (node (ref "X1") (pin "1") (pinfunction "1_1") (pintype "passive"))
    )
    (net (code "33") (name "/RFout") (class "Default")
      (node (ref "C28") (pin "2") (pinfunction "2_2") (pintype "passive"))
      (node (ref "X2") (pin "1") (pinfunction "1_1") (pintype "passive"))
    )
    (net (code "34") (name "/U1") (class "Default")
      (node (ref "C5") (pin "1") (pinfunction "1_1") (pintype "passive"))
      (node (ref "U1") (pin "16") (pinfunction "RFout_16") (pintype "output"))
    )
    (net (code "35") (name "/U2") (class "Default")
      (node (ref "C18") (pin "1") (pinfunction "1_1") (pintype "passive"))
      (node (ref "U2") (pin "5") (pinfunction "RF1_5") (pintype "passive"))
    )
    (net (code "36") (name "/U3") (class "Default")
      (node (ref "C19") (pin "1") (pinfunction "1_1") (pintype "passive"))
      (node (ref "U3") (pin "16") (pinfunction "RFout_16") (pintype "output"))
    )
    (net (code "37") (name "/U4") (class "Default")
      (node (ref "C20") (pin "1") (pinfunction "1_1") (pintype "passive"))
      (node (ref "U4") (pin "5") (pinfunction "RF1_5") (pintype "passive"))
    )
    (net (code "38") (name "/U5") (class "Default")
      (node (ref "C21") (pin "1") (pinfunction "1_1") (pintype "passive"))
      (node (ref "U5") (pin "16") (pinfunction "RFout_16") (pintype "output"))
    )
    (net (code "39") (name "/U6_1") (class "Default")
      (node (ref "C28") (pin "1") (pinfunction "1_1") (pintype "passive"))
      (node (ref "U7") (pin "12") (pinfunction "OUT_1_12") (pintype "output"))
    )
    (net (code "40") (name "/U6_2") (class "Default")
      (node (ref "U7") (pin "29") (pinfunction "OUT_2_29") (pintype "output"))
      (node (ref "U8") (pin "5") (pinfunction "RF_IN_5") (pintype "input"))
    )
    (net (code "41") (name "/U7") (class "Default")
      (node (ref "C29") (pin "1") (pinfunction "1_1") (pintype "passive"))
      (node (ref "R1") (pin "1") (pinfunction "1_1") (pintype "passive"))
      (node (ref "U8") (pin "2") (pinfunction "RF_OUT_2") (pintype "output"))
      (node (ref "U9") (pin "3") (pinfunction "+IN_3") (pintype "input"))
    )
    (net (code "42") (name "/U9") (class "Default")
      (node (ref "C36") (pin "1") (pinfunction "1_1") (pintype "passive"))
      (node (ref "U6") (pin "16") (pinfunction "RFout_16") (pintype "output"))
    )
    (net (code "43") (name "GND") (class "Default")
      (node (ref "B1") (pin "2") (pinfunction "GND_2") (pintype "passive"))
      (node (ref "B1") (pin "3") (pinfunction "2A_3") (pintype "input"))
      (node (ref "B2") (pin "2") (pinfunction "GND_2") (pintype "passive"))
      (node (ref "B2") (pin "3") (pinfunction "2A_3") (pintype "input"))
      (node (ref "B3") (pin "2") (pinfunction "GND_2") (pintype "passive"))
      (node (ref "B3") (pin "3") (pinfunction "2A_3") (pintype "input"))
      (node (ref "C1") (pin "2") (pinfunction "2_2") (pintype "passive"))
      (node (ref "C10") (pin "2") (pinfunction "2_2") (pintype "passive"))
      (node (ref "C11") (pin "2") (pinfunction "2_2") (pintype "passive"))
      (node (ref "C12") (pin "2") (pinfunction "2_2") (pintype "passive"))
      (node (ref "C13") (pin "2") (pinfunction "2_2") (pintype "passive"))
      (node (ref "C14") (pin "2") (pinfunction "2_2") (pintype "passive"))
      (node (ref "C15") (pin "2") (pinfunction "2_2") (pintype "passive"))
      (node (ref "C16") (pin "2") (pinfunction "2_2") (pintype "passive"))
      (node (ref "C17") (pin "2") (pinfunction "2_2") (pintype "passive"))
      (node (ref "C2") (pin "2") (pinfunction "2_2") (pintype "passive"))
      (node (ref "C22") (pin "2") (pinfunction "2_2") (pintype "passive"))
      (node (ref "C23") (pin "2") (pinfunction "2_2") (pintype "passive"))
      (node (ref "C24") (pin "2") (pinfunction "2_2") (pintype "passive"))
      (node (ref "C25") (pin "2") (pinfunction "2_2") (pintype "passive"))
      (node (ref "C26") (pin "2") (pinfunction "2_2") (pintype "passive"))
      (node (ref "C27") (pin "2") (pinfunction "2_2") (pintype "passive"))
      (node (ref "C29") (pin "2") (pinfunction "2_2") (pintype "passive"))
      (node (ref "C3") (pin "2") (pinfunction "2_2") (pintype "passive"))
      (node (ref "C30") (pin "2") (pinfunction "2_2") (pintype "passive"))
      (node (ref "C31") (pin "1") (pinfunction "1_1") (pintype "passive"))
      (node (ref "C32") (pin "1") (pinfunction "1_1") (pintype "passive"))
      (node (ref "C33") (pin "2") (pinfunction "2_2") (pintype "passive"))
      (node (ref "C34") (pin "1") (pinfunction "1_1") (pintype "passive"))
      (node (ref "C37") (pin "2") (pinfunction "2_2") (pintype "passive"))
      (node (ref "C38") (pin "2") (pinfunction "2_2") (pintype "passive"))
      (node (ref "C39") (pin "2") (pinfunction "2_2") (pintype "passive"))
      (node (ref "C6") (pin "2") (pinfunction "2_2") (pintype "passive"))
      (node (ref "C7") (pin "2") (pinfunction "2_2") (pintype "passive"))
      (node (ref "C8") (pin "2") (pinfunction "2_2") (pintype "passive"))
      (node (ref "C9") (pin "2") (pinfunction "2_2") (pintype "passive"))
      (node (ref "R1") (pin "2") (pinfunction "2_2") (pintype "passive"))
      (node (ref "R2") (pin "2") (pinfunction "2_2") (pintype "passive"))
      (node (ref "U1") (pin "1") (pinfunction "N/C_1") (pintype "passive"))
      (node (ref "U1") (pin "10") (pinfunction "N/C_10") (pintype "passive"))
      (node (ref "U1") (pin "11") (pinfunction "N/C_11") (pintype "passive"))
      (node (ref "U1") (pin "12") (pinfunction "N/C_12") (pintype "passive"))
      (node (ref "U1") (pin "13") (pinfunction "N/C_13") (pintype "passive"))
      (node (ref "U1") (pin "14") (pinfunction "N/C_14") (pintype "passive"))
      (node (ref "U1") (pin "15") (pinfunction "GND_15") (pintype "power_in"))
      (node (ref "U1") (pin "17") (pinfunction "GND_17") (pintype "power_in"))
      (node (ref "U1") (pin "18") (pinfunction "N/C_18") (pintype "passive"))
      (node (ref "U1") (pin "19") (pinfunction "N/C_19") (pintype "passive"))
      (node (ref "U1") (pin "2") (pinfunction "GND_2") (pintype "power_in"))
      (node (ref "U1") (pin "20") (pinfunction "N/C_20") (pintype "passive"))
      (node (ref "U1") (pin "22") (pinfunction "N/C_22") (pintype "passive"))
      (node (ref "U1") (pin "23") (pinfunction "N/C_23") (pintype "passive"))
      (node (ref "U1") (pin "24") (pinfunction "N/C_24") (pintype "passive"))
      (node (ref "U1") (pin "25") (pinfunction "BASE_25") (pintype "power_in"))
      (node (ref "U1") (pin "4") (pinfunction "GND_4") (pintype "power_in"))
      (node (ref "U1") (pin "5") (pinfunction "N/C_5") (pintype "passive"))
      (node (ref "U1") (pin "6") (pinfunction "N/C_6") (pintype "passive"))
      (node (ref "U1") (pin "7") (pinfunction "N/C_7") (pintype "passive"))
      (node (ref "U1") (pin "8") (pinfunction "N/C_8") (pintype "passive"))
      (node (ref "U1") (pin "9") (pinfunction "N/C_9") (pintype "passive"))
      (node (ref "U2") (pin "10") (pinfunction "N/C_5_10") (pintype "passive"))
      (node (ref "U2") (pin "11") (pinfunction "N/C_6_11") (pintype "passive"))
      (node (ref "U2") (pin "12") (pinfunction "N/C_7_12") (pintype "passive"))
      (node (ref "U2") (pin "13") (pinfunction "N/C_8_13") (pintype "passive"))
      (node (ref "U2") (pin "15") (pinfunction "GND_2_15") (pintype "passive"))
      (node (ref "U2") (pin "16") (pinfunction "N/C_9_16") (pintype "passive"))
      (node (ref "U2") (pin "19") (pinfunction "PUP_19") (pintype "passive"))
      (node (ref "U2") (pin "21") (pinfunction "ASM1_21") (pintype "passive"))
      (node (ref "U2") (pin "22") (pinfunction "ASM2_22") (pintype "passive"))
      (node (ref "U2") (pin "25") (pinfunction "EP_25") (pintype "passive"))
      (node (ref "U2") (pin "4") (pinfunction "GND_1_4") (pintype "passive"))
      (node (ref "U2") (pin "6") (pinfunction "N/C_1_6") (pintype "passive"))
      (node (ref "U2") (pin "7") (pinfunction "N/C_2_7") (pintype "passive"))
      (node (ref "U2") (pin "8") (pinfunction "N/C_3_8") (pintype "passive"))
      (node (ref "U2") (pin "9") (pinfunction "N/C_4_9") (pintype "passive"))
      (node (ref "U3") (pin "1") (pinfunction "N/C_1") (pintype "passive"))
      (node (ref "U3") (pin "10") (pinfunction "N/C_10") (pintype "passive"))
      (node (ref "U3") (pin "11") (pinfunction "N/C_11") (pintype "passive"))
      (node (ref "U3") (pin "12") (pinfunction "N/C_12") (pintype "passive"))
      (node (ref "U3") (pin "13") (pinfunction "N/C_13") (pintype "passive"))
      (node (ref "U3") (pin "14") (pinfunction "N/C_14") (pintype "passive"))
      (node (ref "U3") (pin "15") (pinfunction "GND_15") (pintype "power_in"))
      (node (ref "U3") (pin "17") (pinfunction "GND_17") (pintype "power_in"))
      (node (ref "U3") (pin "18") (pinfunction "N/C_18") (pintype "passive"))
      (node (ref "U3") (pin "19") (pinfunction "N/C_19") (pintype "passive"))
      (node (ref "U3") (pin "2") (pinfunction "GND_2") (pintype "power_in"))
      (node (ref "U3") (pin "20") (pinfunction "N/C_20") (pintype "passive"))
      (node (ref "U3") (pin "22") (pinfunction "N/C_22") (pintype "passive"))
      (node (ref "U3") (pin "23") (pinfunction "N/C_23") (pintype "passive"))
      (node (ref "U3") (pin "24") (pinfunction "N/C_24") (pintype "passive"))
      (node (ref "U3") (pin "25") (pinfunction "BASE_25") (pintype "power_in"))
      (node (ref "U3") (pin "4") (pinfunction "GND_4") (pintype "power_in"))
      (node (ref "U3") (pin "5") (pinfunction "N/C_5") (pintype "passive"))
      (node (ref "U3") (pin "6") (pinfunction "N/C_6") (pintype "passive"))
      (node (ref "U3") (pin "7") (pinfunction "N/C_7") (pintype "passive"))
      (node (ref "U3") (pin "8") (pinfunction "N/C_8") (pintype "passive"))
      (node (ref "U3") (pin "9") (pinfunction "N/C_9") (pintype "passive"))
      (node (ref "U4") (pin "10") (pinfunction "N/C_5_10") (pintype "passive"))
      (node (ref "U4") (pin "11") (pinfunction "N/C_6_11") (pintype "passive"))
      (node (ref "U4") (pin "12") (pinfunction "N/C_7_12") (pintype "passive"))
      (node (ref "U4") (pin "13") (pinfunction "N/C_8_13") (pintype "passive"))
      (node (ref "U4") (pin "15") (pinfunction "GND_2_15") (pintype "passive"))
      (node (ref "U4") (pin "16") (pinfunction "N/C_9_16") (pintype "passive"))
      (node (ref "U4") (pin "19") (pinfunction "PUP_19") (pintype "passive"))
      (node (ref "U4") (pin "21") (pinfunction "ASM1_21") (pintype "passive"))
      (node (ref "U4") (pin "22") (pinfunction "ASM2_22") (pintype "passive"))
      (node (ref "U4") (pin "25") (pinfunction "EP_25") (pintype "passive"))
      (node (ref "U4") (pin "4") (pinfunction "GND_1_4") (pintype "passive"))
      (node (ref "U4") (pin "6") (pinfunction "N/C_1_6") (pintype "passive"))
      (node (ref "U4") (pin "7") (pinfunction "N/C_2_7") (pintype "passive"))
      (node (ref "U4") (pin "8") (pinfunction "N/C_3_8") (pintype "passive"))
      (node (ref "U4") (pin "9") (pinfunction "N/C_4_9") (pintype "passive"))
      (node (ref "U5") (pin "1") (pinfunction "N/C_1") (pintype "passive"))
      (node (ref "U5") (pin "10") (pinfunction "N/C_10") (pintype "passive"))
      (node (ref "U5") (pin "11") (pinfunction "N/C_11") (pintype "passive"))
      (node (ref "U5") (pin "12") (pinfunction "N/C_12") (pintype "passive"))
      (node (ref "U5") (pin "13") (pinfunction "N/C_13") (pintype "passive"))
      (node (ref "U5") (pin "14") (pinfunction "N/C_14") (pintype "passive"))
      (node (ref "U5") (pin "15") (pinfunction "GND_15") (pintype "power_in"))
      (node (ref "U5") (pin "17") (pinfunction "GND_17") (pintype "power_in"))
      (node (ref "U5") (pin "18") (pinfunction "N/C_18") (pintype "passive"))
      (node (ref "U5") (pin "19") (pinfunction "N/C_19") (pintype "passive"))
      (node (ref "U5") (pin "2") (pinfunction "GND_2") (pintype "power_in"))
      (node (ref "U5") (pin "20") (pinfunction "N/C_20") (pintype "passive"))
      (node (ref "U5") (pin "22") (pinfunction "N/C_22") (pintype "passive"))
      (node (ref "U5") (pin "23") (pinfunction "N/C_23") (pintype "passive"))
      (node (ref "U5") (pin "24") (pinfunction "N/C_24") (pintype "passive"))
      (node (ref "U5") (pin "25") (pinfunction "BASE_25") (pintype "power_in"))
      (node (ref "U5") (pin "4") (pinfunction "GND_4") (pintype "power_in"))
      (node (ref "U5") (pin "5") (pinfunction "N/C_5") (pintype "passive"))
      (node (ref "U5") (pin "6") (pinfunction "N/C_6") (pintype "passive"))
      (node (ref "U5") (pin "7") (pinfunction "N/C_7") (pintype "passive"))
      (node (ref "U5") (pin "8") (pinfunction "N/C_8") (pintype "passive"))
      (node (ref "U5") (pin "9") (pinfunction "N/C_9") (pintype "passive"))
      (node (ref "U6") (pin "1") (pinfunction "N/C_1") (pintype "passive"))
      (node (ref "U6") (pin "10") (pinfunction "N/C_10") (pintype "passive"))
      (node (ref "U6") (pin "11") (pinfunction "N/C_11") (pintype "passive"))
      (node (ref "U6") (pin "12") (pinfunction "N/C_12") (pintype "passive"))
      (node (ref "U6") (pin "13") (pinfunction "N/C_13") (pintype "passive"))
      (node (ref "U6") (pin "14") (pinfunction "N/C_14") (pintype "passive"))
      (node (ref "U6") (pin "15") (pinfunction "GND_15") (pintype "power_in"))
      (node (ref "U6") (pin "17") (pinfunction "GND_17") (pintype "power_in"))
      (node (ref "U6") (pin "18") (pinfunction "N/C_18") (pintype "passive"))
      (node (ref "U6") (pin "19") (pinfunction "N/C_19") (pintype "passive"))
      (node (ref "U6") (pin "2") (pinfunction "GND_2") (pintype "power_in"))
      (node (ref "U6") (pin "20") (pinfunction "N/C_20") (pintype "passive"))
      (node (ref "U6") (pin "22") (pinfunction "N/C_22") (pintype "passive"))
      (node (ref "U6") (pin "23") (pinfunction "N/C_23") (pintype "passive"))
      (node (ref "U6") (pin "24") (pinfunction "N/C_24") (pintype "passive"))
      (node (ref "U6") (pin "25") (pinfunction "BASE_25") (pintype "power_in"))
      (node (ref "U6") (pin "4") (pinfunction "GND_4") (pintype "power_in"))
      (node (ref "U6") (pin "5") (pinfunction "N/C_5") (pintype "passive"))
      (node (ref "U6") (pin "6") (pinfunction "N/C_6") (pintype "passive"))
      (node (ref "U6") (pin "7") (pinfunction "N/C_7") (pintype "passive"))
      (node (ref "U6") (pin "8") (pinfunction "N/C_8") (pintype "passive"))
      (node (ref "U6") (pin "9") (pinfunction "N/C_9") (pintype "passive"))
      (node (ref "U7") (pin "1") (pinfunction "GND_1") (pintype "passive"))
      (node (ref "U7") (pin "10") (pinfunction "GND_10") (pintype "passive"))
      (node (ref "U7") (pin "11") (pinfunction "GND_11") (pintype "passive"))
      (node (ref "U7") (pin "13") (pinfunction "GND_13") (pintype "passive"))
      (node (ref "U7") (pin "14") (pinfunction "GND_14") (pintype "passive"))
      (node (ref "U7") (pin "15") (pinfunction "GND_15") (pintype "passive"))
      (node (ref "U7") (pin "16") (pinfunction "GND_16") (pintype "passive"))
      (node (ref "U7") (pin "17") (pinfunction "GND_17") (pintype "passive"))
      (node (ref "U7") (pin "18") (pinfunction "GND_18") (pintype "passive"))
      (node (ref "U7") (pin "19") (pinfunction "GND_19") (pintype "passive"))
      (node (ref "U7") (pin "2") (pinfunction "GND_2") (pintype "passive"))
      (node (ref "U7") (pin "20") (pinfunction "GND_20") (pintype "passive"))
      (node (ref "U7") (pin "22") (pinfunction "GND_22") (pintype "passive"))
      (node (ref "U7") (pin "23") (pinfunction "GND_23") (pintype "passive"))
      (node (ref "U7") (pin "24") (pinfunction "GND_24") (pintype "passive"))
      (node (ref "U7") (pin "25") (pinfunction "GND_25") (pintype "passive"))
      (node (ref "U7") (pin "26") (pinfunction "GND_26") (pintype "passive"))
      (node (ref "U7") (pin "27") (pinfunction "GND_27") (pintype "passive"))
      (node (ref "U7") (pin "28") (pinfunction "GND_28") (pintype "passive"))
      (node (ref "U7") (pin "3") (pinfunction "GND_3") (pintype "passive"))
      (node (ref "U7") (pin "30") (pinfunction "GND_30") (pintype "passive"))
      (node (ref "U7") (pin "31") (pinfunction "GND_31") (pintype "passive"))
      (node (ref "U7") (pin "32") (pinfunction "GND_32") (pintype "passive"))
      (node (ref "U7") (pin "33") (pinfunction "GND_33") (pintype "passive"))
      (node (ref "U7") (pin "4") (pinfunction "GND_4") (pintype "passive"))
      (node (ref "U7") (pin "5") (pinfunction "GND_5") (pintype "passive"))
      (node (ref "U7") (pin "6") (pinfunction "GND_6") (pintype "passive"))
      (node (ref "U7") (pin "7") (pinfunction "GND_7") (pintype "passive"))
      (node (ref "U7") (pin "8") (pinfunction "GND_8") (pintype "passive"))
      (node (ref "U7") (pin "9") (pinfunction "GND_9") (pintype "passive"))
      (node (ref "U8") (pin "1") (pinfunction "GND_1") (pintype "passive"))
      (node (ref "U8") (pin "4") (pinfunction "GND_4") (pintype "passive"))
      (node (ref "U8") (pin "6") (pinfunction "GND_6") (pintype "passive"))
      (node (ref "U8") (pin "7") (pinfunction "BASE_7") (pintype "passive"))
      (node (ref "U9") (pin "2") (pinfunction "-VS_2") (pintype "power_in"))
      (node (ref "X1") (pin "2") (pinfunction "2_2") (pintype "passive"))
      (node (ref "X1") (pin "3") (pinfunction "3_3") (pintype "passive"))
      (node (ref "X2") (pin "2") (pinfunction "2_2") (pintype "passive"))
      (node (ref "X2") (pin "3") (pinfunction "3_3") (pintype "passive"))
    )
    (net (code "44") (name "unconnected-(B1-2Y-Pad4)") (class "Default")
      (node (ref "B1") (pin "4") (pinfunction "2Y_4") (pintype "output"))
    )
    (net (code "45") (name "unconnected-(B2-2Y-Pad4)") (class "Default")
      (node (ref "B2") (pin "4") (pinfunction "2Y_4") (pintype "output"))
    )
    (net (code "46") (name "unconnected-(B3-2Y-Pad4)") (class "Default")
      (node (ref "B3") (pin "4") (pinfunction "2Y_4") (pintype "output"))
    )
    (net (code "47") (name "unconnected-(U2-SEROUT-Pad18)") (class "Default")
      (node (ref "U2") (pin "18") (pinfunction "SEROUT_18") (pintype "passive"))
    )
  )
)
